# ClockCubed_v1.net
KiCad netlist of a schematic drawn in EAGLE
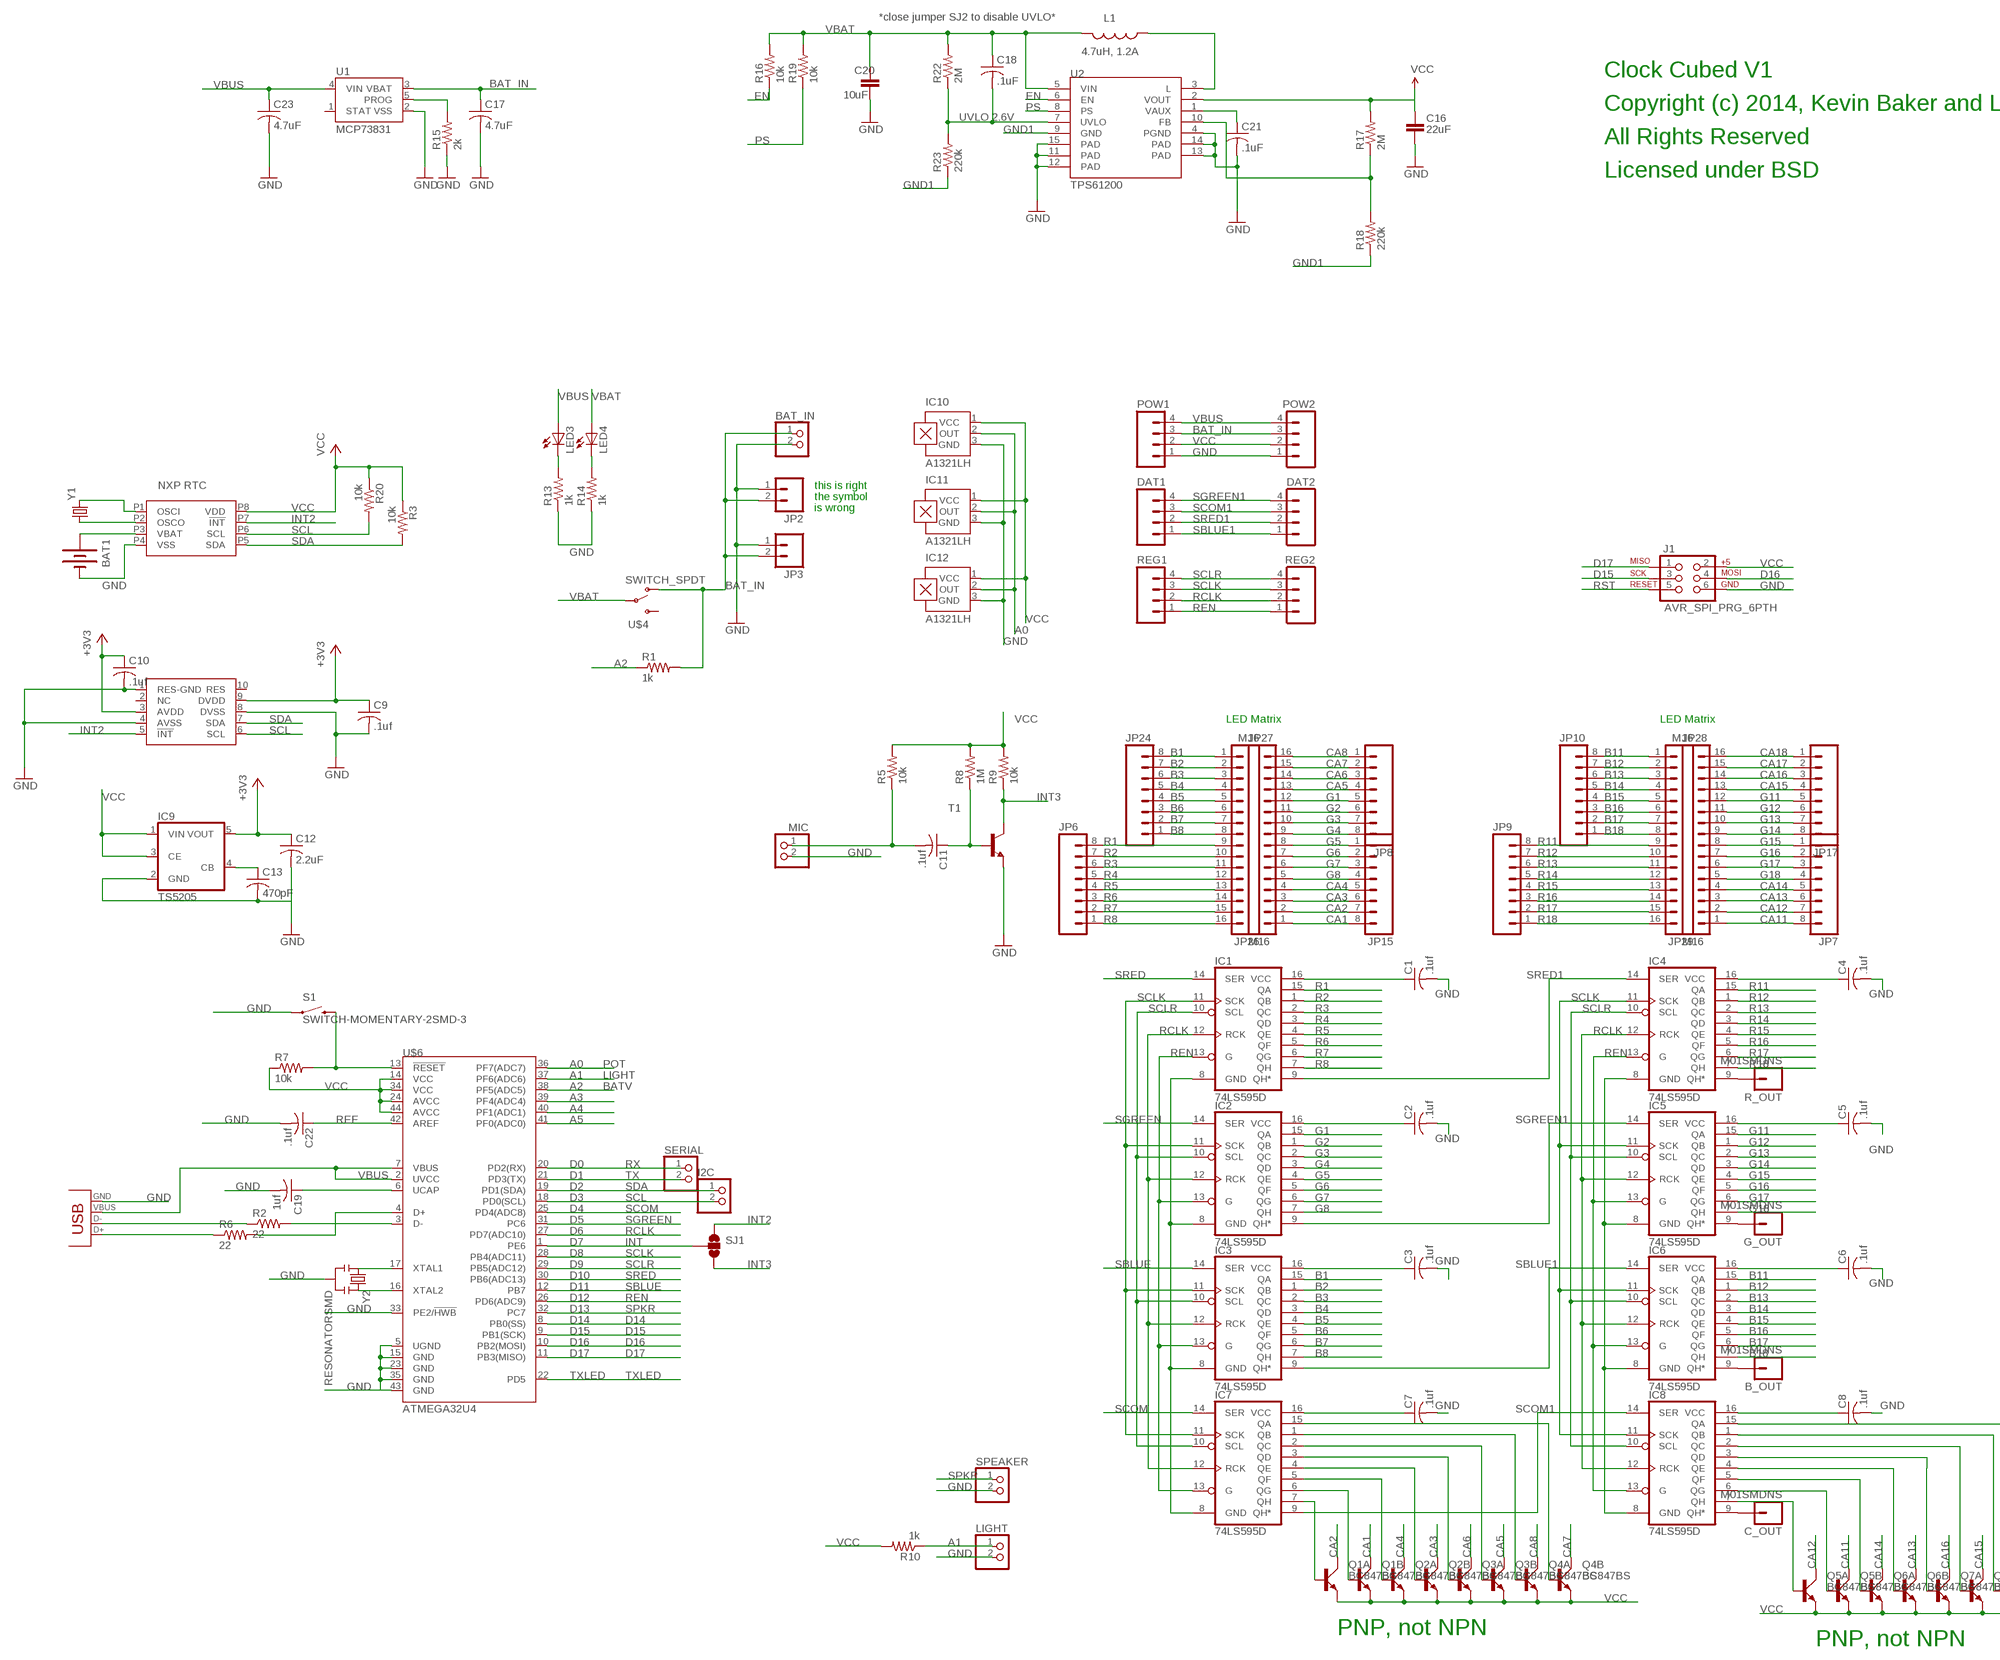
[diagram p0: schematic, sheet 1, part 1 of 2]
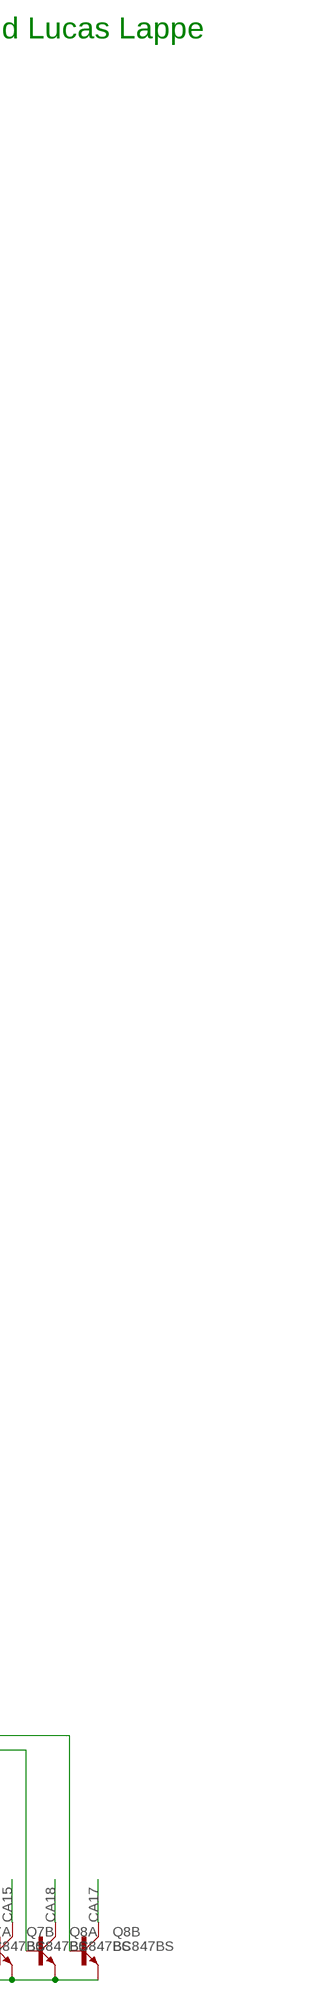
[diagram p1: schematic, sheet 1, part 2 of 2]

(export (version "E")
  (design (tool "Eeschema 10.0.6"))
  (components
    (comp (ref "BAT1")
      (value "BATTERY12MM")
      (footprint "eagle-import:BATTCON_12MM")
      (libsource (lib "eagle-import") (part "BATTERY12MM"))
    )
    (comp (ref "BAT_IN")
      (value "PINHD-1X2")
      (footprint "eagle-import:1X02")
      (libsource (lib "eagle-import") (part "PINHD-1X2"))
    )
    (comp (ref "B_OUT")
      (value "M01SMDNS")
      (footprint "eagle-import:1X01NS")
      (libsource (lib "eagle-import") (part "M01SMDNS"))
    )
    (comp (ref "C1")
      (value ".1uf")
      (footprint "eagle-import:C0603")
      (libsource (lib "eagle-import") (part "C-USC0603"))
    )
    (comp (ref "C2")
      (value ".1uf")
      (footprint "eagle-import:C0603")
      (libsource (lib "eagle-import") (part "C-USC0603"))
    )
    (comp (ref "C3")
      (value ".1uf")
      (footprint "eagle-import:C0603")
      (libsource (lib "eagle-import") (part "C-USC0603"))
    )
    (comp (ref "C4")
      (value ".1uf")
      (footprint "eagle-import:C0603")
      (libsource (lib "eagle-import") (part "C-USC0603"))
    )
    (comp (ref "C5")
      (value ".1uf")
      (footprint "eagle-import:C0603")
      (libsource (lib "eagle-import") (part "C-USC0603"))
    )
    (comp (ref "C6")
      (value ".1uf")
      (footprint "eagle-import:C0603")
      (libsource (lib "eagle-import") (part "C-USC0603"))
    )
    (comp (ref "C7")
      (value ".1uf")
      (footprint "eagle-import:C0603")
      (libsource (lib "eagle-import") (part "C-USC0603"))
    )
    (comp (ref "C8")
      (value ".1uf")
      (footprint "eagle-import:C0603")
      (libsource (lib "eagle-import") (part "C-USC0603"))
    )
    (comp (ref "C9")
      (value ".1uf")
      (footprint "eagle-import:C0603")
      (libsource (lib "eagle-import") (part "C-USC0603"))
    )
    (comp (ref "C10")
      (value ".1uf")
      (footprint "eagle-import:C0603")
      (libsource (lib "eagle-import") (part "C-USC0603"))
    )
    (comp (ref "C11")
      (value ".1uf")
      (footprint "eagle-import:C0603")
      (libsource (lib "eagle-import") (part "C-USC0603"))
    )
    (comp (ref "C12")
      (value "2.2uF")
      (footprint "eagle-import:C0603")
      (libsource (lib "eagle-import") (part "C-USC0603"))
    )
    (comp (ref "C13")
      (value "470pF")
      (footprint "eagle-import:C0603")
      (libsource (lib "eagle-import") (part "C-USC0603"))
    )
    (comp (ref "C16")
      (value "22uF")
      (footprint "eagle-import:0805")
      (libsource (lib "eagle-import") (part "CAP0805"))
    )
    (comp (ref "C17")
      (value "4.7uF")
      (footprint "eagle-import:C0603")
      (libsource (lib "eagle-import") (part "C-USC0603"))
    )
    (comp (ref "C18")
      (value ".1uF")
      (footprint "eagle-import:C0603")
      (libsource (lib "eagle-import") (part "C-USC0603"))
    )
    (comp (ref "C19")
      (value "1uf")
      (footprint "eagle-import:C0603")
      (libsource (lib "eagle-import") (part "C-USC0603"))
    )
    (comp (ref "C20")
      (value "10uF")
      (footprint "eagle-import:1206")
      (libsource (lib "eagle-import") (part "CAP1206"))
    )
    (comp (ref "C21")
      (value ".1uF")
      (footprint "eagle-import:C0603")
      (libsource (lib "eagle-import") (part "C-USC0603"))
    )
    (comp (ref "C22")
      (value ".1uf")
      (footprint "eagle-import:C0603")
      (libsource (lib "eagle-import") (part "C-USC0603"))
    )
    (comp (ref "C23")
      (value "4.7uF")
      (footprint "eagle-import:C0603")
      (libsource (lib "eagle-import") (part "C-USC0603"))
    )
    (comp (ref "C_OUT")
      (value "M01SMDNS")
      (footprint "eagle-import:1X01NS")
      (libsource (lib "eagle-import") (part "M01SMDNS"))
    )
    (comp (ref "DAT1")
      (value "M04PTH")
      (footprint "eagle-import:1X04")
      (libsource (lib "eagle-import") (part "M04PTH"))
    )
    (comp (ref "DAT2")
      (value "M04PTH")
      (footprint "eagle-import:1X04")
      (libsource (lib "eagle-import") (part "M04PTH"))
    )
    (comp (ref "G_OUT")
      (value "M01SMDNS")
      (footprint "eagle-import:1X01NS")
      (libsource (lib "eagle-import") (part "M01SMDNS"))
    )
    (comp (ref "I2C")
      (value "PINHD-1X2")
      (footprint "eagle-import:1X02")
      (libsource (lib "eagle-import") (part "PINHD-1X2"))
    )
    (comp (ref "IC1")
      (value "74LS595D")
      (footprint "eagle-import:SO16")
      (libsource (lib "eagle-import") (part "74595DLS"))
    )
    (comp (ref "IC2")
      (value "74LS595D")
      (footprint "eagle-import:SO16")
      (libsource (lib "eagle-import") (part "74595DLS"))
    )
    (comp (ref "IC3")
      (value "74LS595D")
      (footprint "eagle-import:SO16")
      (libsource (lib "eagle-import") (part "74595DLS"))
    )
    (comp (ref "IC4")
      (value "74LS595D")
      (footprint "eagle-import:SO16")
      (libsource (lib "eagle-import") (part "74595DLS"))
    )
    (comp (ref "IC5")
      (value "74LS595D")
      (footprint "eagle-import:SO16")
      (libsource (lib "eagle-import") (part "74595DLS"))
    )
    (comp (ref "IC6")
      (value "74LS595D")
      (footprint "eagle-import:SO16")
      (libsource (lib "eagle-import") (part "74595DLS"))
    )
    (comp (ref "IC7")
      (value "74LS595D")
      (footprint "eagle-import:SO16")
      (libsource (lib "eagle-import") (part "74595DLS"))
    )
    (comp (ref "IC8")
      (value "74LS595D")
      (footprint "eagle-import:SO16")
      (libsource (lib "eagle-import") (part "74595DLS"))
    )
    (comp (ref "IC9")
      (value "TS5205")
      (footprint "eagle-import:SOT25")
      (libsource (lib "eagle-import") (part "TS5205"))
    )
    (comp (ref "IC10")
      (value "A1321LH")
      (footprint "eagle-import:SOT23-W")
      (fields (field (name "MF") "ALLEGRO MICROSYSTEMS, INC.") (field (name "MPN") "A1321LLHLT-T"))
      (libsource (lib "eagle-import") (part "A13?LH21"))
    )
    (comp (ref "IC11")
      (value "A1321LH")
      (footprint "eagle-import:SOT23-W")
      (fields (field (name "MF") "ALLEGRO MICROSYSTEMS, INC.") (field (name "MPN") "A1321LLHLT-T"))
      (libsource (lib "eagle-import") (part "A13?LH21"))
    )
    (comp (ref "IC12")
      (value "A1321LH")
      (footprint "eagle-import:SOT23-W")
      (fields (field (name "MF") "ALLEGRO MICROSYSTEMS, INC.") (field (name "MPN") "A1321LLHLT-T"))
      (libsource (lib "eagle-import") (part "A13?LH21"))
    )
    (comp (ref "J1")
      (value "AVR_SPI_PRG_6PTH")
      (footprint "eagle-import:2X3")
      (libsource (lib "eagle-import") (part "AVR_SPI_PRG_6PTH"))
    )
    (comp (ref "JP2")
      (value "M02JST-PTH-2")
      (footprint "eagle-import:JST-2-PTH")
      (libsource (lib "eagle-import") (part "M02JST-PTH-2"))
    )
    (comp (ref "JP3")
      (value "M02JST-PTH-2")
      (footprint "eagle-import:JST-2-PTH")
      (libsource (lib "eagle-import") (part "M02JST-PTH-2"))
    )
    (comp (ref "JP6")
      (value "M08SMD-COMBO")
      (footprint "eagle-import:1X08_SMD_COMBINED")
      (libsource (lib "eagle-import") (part "M08SMD-COMBO"))
    )
    (comp (ref "JP7")
      (value "M08SMD-COMBO")
      (footprint "eagle-import:1X08_SMD_COMBINED")
      (libsource (lib "eagle-import") (part "M08SMD-COMBO"))
    )
    (comp (ref "JP8")
      (value "M08SMD-COMBO")
      (footprint "eagle-import:1X08_SMD_COMBINED")
      (libsource (lib "eagle-import") (part "M08SMD-COMBO"))
    )
    (comp (ref "JP9")
      (value "M08SMD-COMBO")
      (footprint "eagle-import:1X08_SMD_COMBINED")
      (libsource (lib "eagle-import") (part "M08SMD-COMBO"))
    )
    (comp (ref "JP10")
      (value "M08SMD-COMBO")
      (footprint "eagle-import:1X08_SMD_COMBINED")
      (libsource (lib "eagle-import") (part "M08SMD-COMBO"))
    )
    (comp (ref "JP15")
      (value "M08SMD-COMBO")
      (footprint "eagle-import:1X08_SMD_COMBINED")
      (libsource (lib "eagle-import") (part "M08SMD-COMBO"))
    )
    (comp (ref "JP17")
      (value "M08SMD-COMBO")
      (footprint "eagle-import:1X08_SMD_COMBINED")
      (libsource (lib "eagle-import") (part "M08SMD-COMBO"))
    )
    (comp (ref "JP24")
      (value "M08SMD-COMBO")
      (footprint "eagle-import:1X08_SMD_COMBINED")
      (libsource (lib "eagle-import") (part "M08SMD-COMBO"))
    )
    (comp (ref "JP26")
      (value "M16")
      (footprint "eagle-import:1X16_NS")
      (libsource (lib "eagle-import") (part "M16"))
    )
    (comp (ref "JP27")
      (value "M16")
      (footprint "eagle-import:1X16_NS")
      (libsource (lib "eagle-import") (part "M16"))
    )
    (comp (ref "JP28")
      (value "M16")
      (footprint "eagle-import:1X16_NS")
      (libsource (lib "eagle-import") (part "M16"))
    )
    (comp (ref "JP29")
      (value "M16")
      (footprint "eagle-import:1X16_NS")
      (libsource (lib "eagle-import") (part "M16"))
    )
    (comp (ref "L1")
      (value "4.7uH, 1.2A")
      (footprint "eagle-import:CDRH2D09")
      (libsource (lib "eagle-import") (part "INDUCTOR."))
    )
    (comp (ref "LED3")
      (value "LEDCHIPLED_0805")
      (footprint "eagle-import:CHIPLED_0805")
      (libsource (lib "eagle-import") (part "LEDCHIPLED_0805"))
    )
    (comp (ref "LED4")
      (value "LEDCHIPLED_0805")
      (footprint "eagle-import:CHIPLED_0805")
      (libsource (lib "eagle-import") (part "LEDCHIPLED_0805"))
    )
    (comp (ref "LIGHT")
      (value "PINHD-1X2")
      (footprint "eagle-import:1X02")
      (libsource (lib "eagle-import") (part "PINHD-1X2"))
    )
    (comp (ref "MIC")
      (value "PINHD-1X2")
      (footprint "eagle-import:1X02")
      (libsource (lib "eagle-import") (part "PINHD-1X2"))
    )
    (comp (ref "POW1")
      (value "M04PTH")
      (footprint "eagle-import:1X04")
      (libsource (lib "eagle-import") (part "M04PTH"))
    )
    (comp (ref "POW2")
      (value "M04PTH")
      (footprint "eagle-import:1X04")
      (libsource (lib "eagle-import") (part "M04PTH"))
    )
    (comp (ref "Q1")
      (value "BC847BS")
      (footprint "eagle-import:SOT363_PHILIPS")
      (libsource (lib "eagle-import") (part "BC847BS"))
    )
    (comp (ref "Q2")
      (value "BC847BS")
      (footprint "eagle-import:SOT363_PHILIPS")
      (libsource (lib "eagle-import") (part "BC847BS"))
    )
    (comp (ref "Q3")
      (value "BC847BS")
      (footprint "eagle-import:SOT363_PHILIPS")
      (libsource (lib "eagle-import") (part "BC847BS"))
    )
    (comp (ref "Q4")
      (value "BC847BS")
      (footprint "eagle-import:SOT363_PHILIPS")
      (libsource (lib "eagle-import") (part "BC847BS"))
    )
    (comp (ref "Q5")
      (value "BC847BS")
      (footprint "eagle-import:SOT363_PHILIPS")
      (libsource (lib "eagle-import") (part "BC847BS"))
    )
    (comp (ref "Q6")
      (value "BC847BS")
      (footprint "eagle-import:SOT363_PHILIPS")
      (libsource (lib "eagle-import") (part "BC847BS"))
    )
    (comp (ref "Q7")
      (value "BC847BS")
      (footprint "eagle-import:SOT363_PHILIPS")
      (libsource (lib "eagle-import") (part "BC847BS"))
    )
    (comp (ref "Q8")
      (value "BC847BS")
      (footprint "eagle-import:SOT363_PHILIPS")
      (libsource (lib "eagle-import") (part "BC847BS"))
    )
    (comp (ref "R1")
      (value "1k")
      (footprint "eagle-import:0603-RES")
      (libsource (lib "eagle-import") (part "RESISTOR0603-RES"))
    )
    (comp (ref "R2")
      (value "22")
      (footprint "eagle-import:0603-RES")
      (libsource (lib "eagle-import") (part "RESISTOR0603-RES"))
    )
    (comp (ref "R3")
      (value "10k")
      (footprint "eagle-import:0603-RES")
      (libsource (lib "eagle-import") (part "RESISTOR0603-RES"))
    )
    (comp (ref "R5")
      (value "10k")
      (footprint "eagle-import:0603-RES")
      (libsource (lib "eagle-import") (part "RESISTOR0603-RES"))
    )
    (comp (ref "R6")
      (value "22")
      (footprint "eagle-import:0603-RES")
      (libsource (lib "eagle-import") (part "RESISTOR0603-RES"))
    )
    (comp (ref "R7")
      (value "10k")
      (footprint "eagle-import:0603-RES")
      (libsource (lib "eagle-import") (part "RESISTOR0603-RES"))
    )
    (comp (ref "R8")
      (value "1M")
      (footprint "eagle-import:0603-RES")
      (libsource (lib "eagle-import") (part "RESISTOR0603-RES"))
    )
    (comp (ref "R9")
      (value "10k")
      (footprint "eagle-import:0603-RES")
      (libsource (lib "eagle-import") (part "RESISTOR0603-RES"))
    )
    (comp (ref "R10")
      (value "1k")
      (footprint "eagle-import:0603-RES")
      (libsource (lib "eagle-import") (part "RESISTOR0603-RES"))
    )
    (comp (ref "R13")
      (value "1k")
      (footprint "eagle-import:0603-RES")
      (libsource (lib "eagle-import") (part "RESISTOR0603-RES"))
    )
    (comp (ref "R14")
      (value "1k")
      (footprint "eagle-import:0603-RES")
      (libsource (lib "eagle-import") (part "RESISTOR0603-RES"))
    )
    (comp (ref "R15")
      (value "2k")
      (footprint "eagle-import:0603-RES")
      (libsource (lib "eagle-import") (part "RESISTOR0603-RES"))
    )
    (comp (ref "R16")
      (value "10k")
      (footprint "eagle-import:0603-RES")
      (libsource (lib "eagle-import") (part "RESISTOR0603-RES"))
    )
    (comp (ref "R17")
      (value "2M")
      (footprint "eagle-import:0603-RES")
      (libsource (lib "eagle-import") (part "RESISTOR0603-RES"))
    )
    (comp (ref "R18")
      (value "220k")
      (footprint "eagle-import:0603-RES")
      (libsource (lib "eagle-import") (part "RESISTOR0603-RES"))
    )
    (comp (ref "R19")
      (value "10k")
      (footprint "eagle-import:0603-RES")
      (libsource (lib "eagle-import") (part "RESISTOR0603-RES"))
    )
    (comp (ref "R20")
      (value "10k")
      (footprint "eagle-import:0603-RES")
      (libsource (lib "eagle-import") (part "RESISTOR0603-RES"))
    )
    (comp (ref "R22")
      (value "2M")
      (footprint "eagle-import:0603-RES")
      (libsource (lib "eagle-import") (part "RESISTOR0603-RES"))
    )
    (comp (ref "R23")
      (value "220k")
      (footprint "eagle-import:0603-RES")
      (libsource (lib "eagle-import") (part "RESISTOR0603-RES"))
    )
    (comp (ref "REG1")
      (value "M04PTH")
      (footprint "eagle-import:1X04")
      (libsource (lib "eagle-import") (part "M04PTH"))
    )
    (comp (ref "REG2")
      (value "M04PTH")
      (footprint "eagle-import:1X04")
      (libsource (lib "eagle-import") (part "M04PTH"))
    )
    (comp (ref "R_OUT")
      (value "M01SMDNS")
      (footprint "eagle-import:1X01NS")
      (libsource (lib "eagle-import") (part "M01SMDNS"))
    )
    (comp (ref "S1")
      (value "SWITCH-MOMENTARY-2SMD-3")
      (footprint "eagle-import:TACTILE_SWITCH_SMD-3")
      (libsource (lib "eagle-import") (part "SWITCH-MOMENTARY-2SMD-3"))
    )
    (comp (ref "SERIAL")
      (value "PINHD-1X2")
      (footprint "eagle-import:1X02")
      (libsource (lib "eagle-import") (part "PINHD-1X2"))
    )
    (comp (ref "SJ1")
      (value "SOLDERJUMPER_2WAYS")
      (footprint "eagle-import:SJ_3")
      (libsource (lib "eagle-import") (part "SOLDERJUMPER_2WAYS"))
    )
    (comp (ref "SPEAKER")
      (value "PINHD-1X2")
      (footprint "eagle-import:1X02")
      (libsource (lib "eagle-import") (part "PINHD-1X2"))
    )
    (comp (ref "T1")
      (value "-NPN-SOT23-EBC")
      (footprint "eagle-import:SOT23-EBC")
      (libsource (lib "eagle-import") (part "-NPN-SOT23-EBC"))
    )
    (comp (ref "U$1")
      (value "USB_MICROB")
      (footprint "eagle-import:USB-MICROB")
      (libsource (lib "eagle-import") (part "USB_MICROB"))
    )
    (comp (ref "U$2")
      (value "MMA7660FC")
      (footprint "eagle-import:DFN-10")
      (libsource (lib "eagle-import") (part "MMA7660FC"))
    )
    (comp (ref "U$3")
      (value "NXP-RTC")
      (footprint "eagle-import:HVSON8")
      (libsource (lib "eagle-import") (part "NXP-RTC"))
    )
    (comp (ref "U$4")
      (value "SWITCH_SPDT")
      (footprint "eagle-import:KPS-1290")
      (libsource (lib "eagle-import") (part "SWITCH_SPDT"))
    )
    (comp (ref "U$6")
      (value "ATMEGA32U4")
      (footprint "eagle-import:TQFP44")
      (libsource (lib "eagle-import") (part "ATMEGA32U4"))
    )
    (comp (ref "U1")
      (value "MCP73831")
      (footprint "eagle-import:SOT23-5")
      (libsource (lib "eagle-import") (part "MCP73831"))
    )
    (comp (ref "U2")
      (value "TPS61200")
      (footprint "eagle-import:QFN-10_PAD")
      (libsource (lib "eagle-import") (part "TPS61200"))
    )
    (comp (ref "Y1")
      (value "CRYSTAL5X2")
      (footprint "eagle-import:CRYSTAL-SMD-5X2")
      (libsource (lib "eagle-import") (part "CRYSTAL5X2"))
    )
    (comp (ref "Y2")
      (value "RESONATORSMD")
      (footprint "eagle-import:RESONATOR-SMD")
      (libsource (lib "eagle-import") (part "RESONATORSMD"))
    )
  )
  (nets
    (net (code "1") (name "+3V3") (class "Default")
      (node (ref "C10") (pin "1") (pinfunction "1_1") (pintype "passive"))
      (node (ref "C12") (pin "1") (pinfunction "1_1") (pintype "passive"))
      (node (ref "C9") (pin "1") (pinfunction "1_1") (pintype "passive"))
      (node (ref "IC9") (pin "5") (pinfunction "VOUT_5") (pintype "passive"))
      (node (ref "U$2") (pin "3") (pinfunction "AVDD_3") (pintype "bidirectional"))
      (node (ref "U$2") (pin "9") (pinfunction "DVDD_9") (pintype "bidirectional"))
    )
    (net (code "2") (name "/A0") (class "Default")
      (node (ref "IC10") (pin "2") (pinfunction "OUT_2") (pintype "output"))
      (node (ref "IC11") (pin "2") (pinfunction "OUT_2") (pintype "output"))
      (node (ref "IC12") (pin "2") (pinfunction "OUT_2") (pintype "output"))
      (node (ref "U$6") (pin "36") (pinfunction "PF7(ADC7)_36") (pintype "bidirectional"))
    )
    (net (code "3") (name "/A1") (class "Default")
      (node (ref "LIGHT") (pin "1") (pinfunction "1_1") (pintype "passive"))
      (node (ref "R10") (pin "1") (pinfunction "1_1") (pintype "passive"))
      (node (ref "U$6") (pin "37") (pinfunction "PF6(ADC6)_37") (pintype "bidirectional"))
    )
    (net (code "4") (name "/A2") (class "Default")
      (node (ref "R1") (pin "1") (pinfunction "1_1") (pintype "passive"))
      (node (ref "U$6") (pin "38") (pinfunction "PF5(ADC5)_38") (pintype "bidirectional"))
    )
    (net (code "5") (name "/A3") (class "Default")
      (node (ref "U$6") (pin "39") (pinfunction "PF4(ADC4)_39") (pintype "bidirectional"))
    )
    (net (code "6") (name "/A4") (class "Default")
      (node (ref "U$6") (pin "40") (pinfunction "PF1(ADC1)_40") (pintype "bidirectional"))
    )
    (net (code "7") (name "/A5") (class "Default")
      (node (ref "U$6") (pin "41") (pinfunction "PF0(ADC0)_41") (pintype "bidirectional"))
    )
    (net (code "8") (name "/B1") (class "Default")
      (node (ref "IC3") (pin "15") (pinfunction "QA_15") (pintype "tri_state"))
      (node (ref "JP24") (pin "8") (pinfunction "8_8") (pintype "passive"))
      (node (ref "JP26") (pin "1") (pinfunction "1_1") (pintype "passive"))
    )
    (net (code "9") (name "/B2") (class "Default")
      (node (ref "IC3") (pin "1") (pinfunction "QB_1") (pintype "tri_state"))
      (node (ref "JP24") (pin "7") (pinfunction "7_7") (pintype "passive"))
      (node (ref "JP26") (pin "2") (pinfunction "2_2") (pintype "passive"))
    )
    (net (code "10") (name "/B3") (class "Default")
      (node (ref "IC3") (pin "2") (pinfunction "QC_2") (pintype "tri_state"))
      (node (ref "JP24") (pin "6") (pinfunction "6_6") (pintype "passive"))
      (node (ref "JP26") (pin "3") (pinfunction "3_3") (pintype "passive"))
    )
    (net (code "11") (name "/B4") (class "Default")
      (node (ref "IC3") (pin "3") (pinfunction "QD_3") (pintype "tri_state"))
      (node (ref "JP24") (pin "5") (pinfunction "5_5") (pintype "passive"))
      (node (ref "JP26") (pin "4") (pinfunction "4_4") (pintype "passive"))
    )
    (net (code "12") (name "/B5") (class "Default")
      (node (ref "IC3") (pin "4") (pinfunction "QE_4") (pintype "tri_state"))
      (node (ref "JP24") (pin "4") (pinfunction "4_4") (pintype "passive"))
      (node (ref "JP26") (pin "5") (pinfunction "5_5") (pintype "passive"))
    )
    (net (code "13") (name "/B6") (class "Default")
      (node (ref "IC3") (pin "5") (pinfunction "QF_5") (pintype "tri_state"))
      (node (ref "JP24") (pin "3") (pinfunction "3_3") (pintype "passive"))
      (node (ref "JP26") (pin "6") (pinfunction "6_6") (pintype "passive"))
    )
    (net (code "14") (name "/B7") (class "Default")
      (node (ref "IC3") (pin "6") (pinfunction "QG_6") (pintype "tri_state"))
      (node (ref "JP24") (pin "2") (pinfunction "2_2") (pintype "passive"))
      (node (ref "JP26") (pin "7") (pinfunction "7_7") (pintype "passive"))
    )
    (net (code "15") (name "/B8") (class "Default")
      (node (ref "IC3") (pin "7") (pinfunction "QH_7") (pintype "tri_state"))
      (node (ref "JP24") (pin "1") (pinfunction "1_1") (pintype "passive"))
      (node (ref "JP26") (pin "8") (pinfunction "8_8") (pintype "passive"))
    )
    (net (code "16") (name "/B11") (class "Default")
      (node (ref "IC6") (pin "15") (pinfunction "QA_15") (pintype "tri_state"))
      (node (ref "JP10") (pin "8") (pinfunction "8_8") (pintype "passive"))
      (node (ref "JP29") (pin "1") (pinfunction "1_1") (pintype "passive"))
    )
    (net (code "17") (name "/B12") (class "Default")
      (node (ref "IC6") (pin "1") (pinfunction "QB_1") (pintype "tri_state"))
      (node (ref "JP10") (pin "7") (pinfunction "7_7") (pintype "passive"))
      (node (ref "JP29") (pin "2") (pinfunction "2_2") (pintype "passive"))
    )
    (net (code "18") (name "/B13") (class "Default")
      (node (ref "IC6") (pin "2") (pinfunction "QC_2") (pintype "tri_state"))
      (node (ref "JP10") (pin "6") (pinfunction "6_6") (pintype "passive"))
      (node (ref "JP29") (pin "3") (pinfunction "3_3") (pintype "passive"))
    )
    (net (code "19") (name "/B14") (class "Default")
      (node (ref "IC6") (pin "3") (pinfunction "QD_3") (pintype "tri_state"))
      (node (ref "JP10") (pin "5") (pinfunction "5_5") (pintype "passive"))
      (node (ref "JP29") (pin "4") (pinfunction "4_4") (pintype "passive"))
    )
    (net (code "20") (name "/B15") (class "Default")
      (node (ref "IC6") (pin "4") (pinfunction "QE_4") (pintype "tri_state"))
      (node (ref "JP10") (pin "4") (pinfunction "4_4") (pintype "passive"))
      (node (ref "JP29") (pin "5") (pinfunction "5_5") (pintype "passive"))
    )
    (net (code "21") (name "/B16") (class "Default")
      (node (ref "IC6") (pin "5") (pinfunction "QF_5") (pintype "tri_state"))
      (node (ref "JP10") (pin "3") (pinfunction "3_3") (pintype "passive"))
      (node (ref "JP29") (pin "6") (pinfunction "6_6") (pintype "passive"))
    )
    (net (code "22") (name "/B17") (class "Default")
      (node (ref "IC6") (pin "6") (pinfunction "QG_6") (pintype "tri_state"))
      (node (ref "JP10") (pin "2") (pinfunction "2_2") (pintype "passive"))
      (node (ref "JP29") (pin "7") (pinfunction "7_7") (pintype "passive"))
    )
    (net (code "23") (name "/B18") (class "Default")
      (node (ref "IC6") (pin "7") (pinfunction "QH_7") (pintype "tri_state"))
      (node (ref "JP10") (pin "1") (pinfunction "1_1") (pintype "passive"))
      (node (ref "JP29") (pin "8") (pinfunction "8_8") (pintype "passive"))
    )
    (net (code "24") (name "/BAT_IN") (class "Default")
      (node (ref "BAT_IN") (pin "1") (pinfunction "1_1") (pintype "passive"))
      (node (ref "C17") (pin "1") (pinfunction "1_1") (pintype "passive"))
      (node (ref "JP2") (pin "2") (pinfunction "2_2") (pintype "passive"))
      (node (ref "JP3") (pin "2") (pinfunction "2_2") (pintype "passive"))
      (node (ref "POW1") (pin "3") (pinfunction "3_3") (pintype "passive"))
      (node (ref "POW2") (pin "3") (pinfunction "3_3") (pintype "passive"))
      (node (ref "R1") (pin "2") (pinfunction "2_2") (pintype "passive"))
      (node (ref "U$4") (pin "O") (pinfunction "O_O") (pintype "passive"))
      (node (ref "U1") (pin "3") (pinfunction "VBAT_3") (pintype "power_in"))
    )
    (net (code "25") (name "/CA1") (class "Default")
      (node (ref "JP15") (pin "8") (pinfunction "8_8") (pintype "passive"))
      (node (ref "JP27") (pin "1") (pinfunction "1_1") (pintype "passive"))
      (node (ref "Q1") (pin "3") (pinfunction "C_3") (pintype "passive"))
    )
    (net (code "26") (name "/CA2") (class "Default")
      (node (ref "JP15") (pin "7") (pinfunction "7_7") (pintype "passive"))
      (node (ref "JP27") (pin "2") (pinfunction "2_2") (pintype "passive"))
      (node (ref "Q1") (pin "6") (pinfunction "C_6") (pintype "passive"))
    )
    (net (code "27") (name "/CA3") (class "Default")
      (node (ref "JP15") (pin "6") (pinfunction "6_6") (pintype "passive"))
      (node (ref "JP27") (pin "3") (pinfunction "3_3") (pintype "passive"))
      (node (ref "Q2") (pin "3") (pinfunction "C_3") (pintype "passive"))
    )
    (net (code "28") (name "/CA4") (class "Default")
      (node (ref "JP15") (pin "5") (pinfunction "5_5") (pintype "passive"))
      (node (ref "JP27") (pin "4") (pinfunction "4_4") (pintype "passive"))
      (node (ref "Q2") (pin "6") (pinfunction "C_6") (pintype "passive"))
    )
    (net (code "29") (name "/CA5") (class "Default")
      (node (ref "JP27") (pin "13") (pinfunction "13_13") (pintype "passive"))
      (node (ref "JP8") (pin "4") (pinfunction "4_4") (pintype "passive"))
      (node (ref "Q3") (pin "3") (pinfunction "C_3") (pintype "passive"))
    )
    (net (code "30") (name "/CA6") (class "Default")
      (node (ref "JP27") (pin "14") (pinfunction "14_14") (pintype "passive"))
      (node (ref "JP8") (pin "3") (pinfunction "3_3") (pintype "passive"))
      (node (ref "Q3") (pin "6") (pinfunction "C_6") (pintype "passive"))
    )
    (net (code "31") (name "/CA7") (class "Default")
      (node (ref "JP27") (pin "15") (pinfunction "15_15") (pintype "passive"))
      (node (ref "JP8") (pin "2") (pinfunction "2_2") (pintype "passive"))
      (node (ref "Q4") (pin "3") (pinfunction "C_3") (pintype "passive"))
    )
    (net (code "32") (name "/CA8") (class "Default")
      (node (ref "JP27") (pin "16") (pinfunction "16_16") (pintype "passive"))
      (node (ref "JP8") (pin "1") (pinfunction "1_1") (pintype "passive"))
      (node (ref "Q4") (pin "6") (pinfunction "C_6") (pintype "passive"))
    )
    (net (code "33") (name "/CA11") (class "Default")
      (node (ref "JP28") (pin "1") (pinfunction "1_1") (pintype "passive"))
      (node (ref "JP7") (pin "8") (pinfunction "8_8") (pintype "passive"))
      (node (ref "Q5") (pin "3") (pinfunction "C_3") (pintype "passive"))
    )
    (net (code "34") (name "/CA12") (class "Default")
      (node (ref "JP28") (pin "2") (pinfunction "2_2") (pintype "passive"))
      (node (ref "JP7") (pin "7") (pinfunction "7_7") (pintype "passive"))
      (node (ref "Q5") (pin "6") (pinfunction "C_6") (pintype "passive"))
    )
    (net (code "35") (name "/CA13") (class "Default")
      (node (ref "JP28") (pin "3") (pinfunction "3_3") (pintype "passive"))
      (node (ref "JP7") (pin "6") (pinfunction "6_6") (pintype "passive"))
      (node (ref "Q6") (pin "3") (pinfunction "C_3") (pintype "passive"))
    )
    (net (code "36") (name "/CA14") (class "Default")
      (node (ref "JP28") (pin "4") (pinfunction "4_4") (pintype "passive"))
      (node (ref "JP7") (pin "5") (pinfunction "5_5") (pintype "passive"))
      (node (ref "Q6") (pin "6") (pinfunction "C_6") (pintype "passive"))
    )
    (net (code "37") (name "/CA15") (class "Default")
      (node (ref "JP17") (pin "4") (pinfunction "4_4") (pintype "passive"))
      (node (ref "JP28") (pin "13") (pinfunction "13_13") (pintype "passive"))
      (node (ref "Q7") (pin "3") (pinfunction "C_3") (pintype "passive"))
    )
    (net (code "38") (name "/CA16") (class "Default")
      (node (ref "JP17") (pin "3") (pinfunction "3_3") (pintype "passive"))
      (node (ref "JP28") (pin "14") (pinfunction "14_14") (pintype "passive"))
      (node (ref "Q7") (pin "6") (pinfunction "C_6") (pintype "passive"))
    )
    (net (code "39") (name "/CA17") (class "Default")
      (node (ref "JP17") (pin "2") (pinfunction "2_2") (pintype "passive"))
      (node (ref "JP28") (pin "15") (pinfunction "15_15") (pintype "passive"))
      (node (ref "Q8") (pin "3") (pinfunction "C_3") (pintype "passive"))
    )
    (net (code "40") (name "/CA18") (class "Default")
      (node (ref "JP17") (pin "1") (pinfunction "1_1") (pintype "passive"))
      (node (ref "JP28") (pin "16") (pinfunction "16_16") (pintype "passive"))
      (node (ref "Q8") (pin "6") (pinfunction "C_6") (pintype "passive"))
    )
    (net (code "41") (name "/D14") (class "Default")
      (node (ref "U$6") (pin "8") (pinfunction "PB0(SS)_8") (pintype "bidirectional"))
    )
    (net (code "42") (name "/D15") (class "Default")
      (node (ref "J1") (pin "3") (pinfunction "3_3") (pintype "passive"))
      (node (ref "U$6") (pin "9") (pinfunction "PB1(SCK)_9") (pintype "bidirectional"))
    )
    (net (code "43") (name "/D16") (class "Default")
      (node (ref "J1") (pin "4") (pinfunction "4_4") (pintype "passive"))
      (node (ref "U$6") (pin "10") (pinfunction "PB2(MOSI)_10") (pintype "bidirectional"))
    )
    (net (code "44") (name "/D17") (class "Default")
      (node (ref "J1") (pin "1") (pinfunction "1_1") (pintype "passive"))
      (node (ref "U$6") (pin "11") (pinfunction "PB3(MISO)_11") (pintype "bidirectional"))
    )
    (net (code "45") (name "/EN") (class "Default")
      (node (ref "R16") (pin "1") (pinfunction "1_1") (pintype "passive"))
      (node (ref "U2") (pin "6") (pinfunction "EN_6") (pintype "input"))
    )
    (net (code "46") (name "/G1") (class "Default")
      (node (ref "IC2") (pin "15") (pinfunction "QA_15") (pintype "tri_state"))
      (node (ref "JP27") (pin "12") (pinfunction "12_12") (pintype "passive"))
      (node (ref "JP8") (pin "5") (pinfunction "5_5") (pintype "passive"))
    )
    (net (code "47") (name "/G2") (class "Default")
      (node (ref "IC2") (pin "1") (pinfunction "QB_1") (pintype "tri_state"))
      (node (ref "JP27") (pin "11") (pinfunction "11_11") (pintype "passive"))
      (node (ref "JP8") (pin "6") (pinfunction "6_6") (pintype "passive"))
    )
    (net (code "48") (name "/G3") (class "Default")
      (node (ref "IC2") (pin "2") (pinfunction "QC_2") (pintype "tri_state"))
      (node (ref "JP27") (pin "10") (pinfunction "10_10") (pintype "passive"))
      (node (ref "JP8") (pin "7") (pinfunction "7_7") (pintype "passive"))
    )
    (net (code "49") (name "/G4") (class "Default")
      (node (ref "IC2") (pin "3") (pinfunction "QD_3") (pintype "tri_state"))
      (node (ref "JP27") (pin "9") (pinfunction "9_9") (pintype "passive"))
      (node (ref "JP8") (pin "8") (pinfunction "8_8") (pintype "passive"))
    )
    (net (code "50") (name "/G5") (class "Default")
      (node (ref "IC2") (pin "4") (pinfunction "QE_4") (pintype "tri_state"))
      (node (ref "JP15") (pin "1") (pinfunction "1_1") (pintype "passive"))
      (node (ref "JP27") (pin "8") (pinfunction "8_8") (pintype "passive"))
    )
    (net (code "51") (name "/G6") (class "Default")
      (node (ref "IC2") (pin "5") (pinfunction "QF_5") (pintype "tri_state"))
      (node (ref "JP15") (pin "2") (pinfunction "2_2") (pintype "passive"))
      (node (ref "JP27") (pin "7") (pinfunction "7_7") (pintype "passive"))
    )
    (net (code "52") (name "/G7") (class "Default")
      (node (ref "IC2") (pin "6") (pinfunction "QG_6") (pintype "tri_state"))
      (node (ref "JP15") (pin "3") (pinfunction "3_3") (pintype "passive"))
      (node (ref "JP27") (pin "6") (pinfunction "6_6") (pintype "passive"))
    )
    (net (code "53") (name "/G8") (class "Default")
      (node (ref "IC2") (pin "7") (pinfunction "QH_7") (pintype "tri_state"))
      (node (ref "JP15") (pin "4") (pinfunction "4_4") (pintype "passive"))
      (node (ref "JP27") (pin "5") (pinfunction "5_5") (pintype "passive"))
    )
    (net (code "54") (name "/G11") (class "Default")
      (node (ref "IC5") (pin "15") (pinfunction "QA_15") (pintype "tri_state"))
      (node (ref "JP17") (pin "5") (pinfunction "5_5") (pintype "passive"))
      (node (ref "JP28") (pin "12") (pinfunction "12_12") (pintype "passive"))
    )
    (net (code "55") (name "/G12") (class "Default")
      (node (ref "IC5") (pin "1") (pinfunction "QB_1") (pintype "tri_state"))
      (node (ref "JP17") (pin "6") (pinfunction "6_6") (pintype "passive"))
      (node (ref "JP28") (pin "11") (pinfunction "11_11") (pintype "passive"))
    )
    (net (code "56") (name "/G13") (class "Default")
      (node (ref "IC5") (pin "2") (pinfunction "QC_2") (pintype "tri_state"))
      (node (ref "JP17") (pin "7") (pinfunction "7_7") (pintype "passive"))
      (node (ref "JP28") (pin "10") (pinfunction "10_10") (pintype "passive"))
    )
    (net (code "57") (name "/G14") (class "Default")
      (node (ref "IC5") (pin "3") (pinfunction "QD_3") (pintype "tri_state"))
      (node (ref "JP17") (pin "8") (pinfunction "8_8") (pintype "passive"))
      (node (ref "JP28") (pin "9") (pinfunction "9_9") (pintype "passive"))
    )
    (net (code "58") (name "/G15") (class "Default")
      (node (ref "IC5") (pin "4") (pinfunction "QE_4") (pintype "tri_state"))
      (node (ref "JP28") (pin "8") (pinfunction "8_8") (pintype "passive"))
      (node (ref "JP7") (pin "1") (pinfunction "1_1") (pintype "passive"))
    )
    (net (code "59") (name "/G16") (class "Default")
      (node (ref "IC5") (pin "5") (pinfunction "QF_5") (pintype "tri_state"))
      (node (ref "JP28") (pin "7") (pinfunction "7_7") (pintype "passive"))
      (node (ref "JP7") (pin "2") (pinfunction "2_2") (pintype "passive"))
    )
    (net (code "60") (name "/G17") (class "Default")
      (node (ref "IC5") (pin "6") (pinfunction "QG_6") (pintype "tri_state"))
      (node (ref "JP28") (pin "6") (pinfunction "6_6") (pintype "passive"))
      (node (ref "JP7") (pin "3") (pinfunction "3_3") (pintype "passive"))
    )
    (net (code "61") (name "/G18") (class "Default")
      (node (ref "IC5") (pin "7") (pinfunction "QH_7") (pintype "tri_state"))
      (node (ref "JP28") (pin "5") (pinfunction "5_5") (pintype "passive"))
      (node (ref "JP7") (pin "4") (pinfunction "4_4") (pintype "passive"))
    )
    (net (code "62") (name "/GND1") (class "Default")
      (node (ref "R18") (pin "1") (pinfunction "1_1") (pintype "passive"))
      (node (ref "R23") (pin "1") (pinfunction "1_1") (pintype "passive"))
      (node (ref "U2") (pin "9") (pinfunction "GND_9") (pintype "power_in"))
    )
    (net (code "63") (name "/INT") (class "Default")
      (node (ref "SJ1") (pin "2") (pinfunction "2_2") (pintype "passive"))
      (node (ref "U$6") (pin "1") (pinfunction "PE6_1") (pintype "bidirectional"))
    )
    (net (code "64") (name "/INT2") (class "Default")
      (node (ref "SJ1") (pin "1") (pinfunction "1_1") (pintype "passive"))
      (node (ref "U$2") (pin "5") (pinfunction "~{INT}_5") (pintype "bidirectional"))
      (node (ref "U$3") (pin "P7") (pinfunction "~{INT}_P7") (pintype "bidirectional"))
    )
    (net (code "65") (name "/INT3") (class "Default")
      (node (ref "R9") (pin "1") (pinfunction "1_1") (pintype "passive"))
      (node (ref "SJ1") (pin "3") (pinfunction "3_3") (pintype "passive"))
      (node (ref "T1") (pin "C") (pinfunction "C_C") (pintype "passive"))
    )
    (net (code "66") (name "/PS") (class "Default")
      (node (ref "R19") (pin "1") (pinfunction "1_1") (pintype "passive"))
      (node (ref "U2") (pin "8") (pinfunction "PS_8") (pintype "input"))
    )
    (net (code "67") (name "/R1") (class "Default")
      (node (ref "IC1") (pin "15") (pinfunction "QA_15") (pintype "tri_state"))
      (node (ref "JP26") (pin "9") (pinfunction "9_9") (pintype "passive"))
      (node (ref "JP6") (pin "8") (pinfunction "8_8") (pintype "passive"))
    )
    (net (code "68") (name "/R2") (class "Default")
      (node (ref "IC1") (pin "1") (pinfunction "QB_1") (pintype "tri_state"))
      (node (ref "JP26") (pin "10") (pinfunction "10_10") (pintype "passive"))
      (node (ref "JP6") (pin "7") (pinfunction "7_7") (pintype "passive"))
    )
    (net (code "69") (name "/R3") (class "Default")
      (node (ref "IC1") (pin "2") (pinfunction "QC_2") (pintype "tri_state"))
      (node (ref "JP26") (pin "11") (pinfunction "11_11") (pintype "passive"))
      (node (ref "JP6") (pin "6") (pinfunction "6_6") (pintype "passive"))
    )
    (net (code "70") (name "/R4") (class "Default")
      (node (ref "IC1") (pin "3") (pinfunction "QD_3") (pintype "tri_state"))
      (node (ref "JP26") (pin "12") (pinfunction "12_12") (pintype "passive"))
      (node (ref "JP6") (pin "5") (pinfunction "5_5") (pintype "passive"))
    )
    (net (code "71") (name "/R5") (class "Default")
      (node (ref "IC1") (pin "4") (pinfunction "QE_4") (pintype "tri_state"))
      (node (ref "JP26") (pin "13") (pinfunction "13_13") (pintype "passive"))
      (node (ref "JP6") (pin "4") (pinfunction "4_4") (pintype "passive"))
    )
    (net (code "72") (name "/R6") (class "Default")
      (node (ref "IC1") (pin "5") (pinfunction "QF_5") (pintype "tri_state"))
      (node (ref "JP26") (pin "14") (pinfunction "14_14") (pintype "passive"))
      (node (ref "JP6") (pin "3") (pinfunction "3_3") (pintype "passive"))
    )
    (net (code "73") (name "/R7") (class "Default")
      (node (ref "IC1") (pin "6") (pinfunction "QG_6") (pintype "tri_state"))
      (node (ref "JP26") (pin "15") (pinfunction "15_15") (pintype "passive"))
      (node (ref "JP6") (pin "2") (pinfunction "2_2") (pintype "passive"))
    )
    (net (code "74") (name "/R8") (class "Default")
      (node (ref "IC1") (pin "7") (pinfunction "QH_7") (pintype "tri_state"))
      (node (ref "JP26") (pin "16") (pinfunction "16_16") (pintype "passive"))
      (node (ref "JP6") (pin "1") (pinfunction "1_1") (pintype "passive"))
    )
    (net (code "75") (name "/R11") (class "Default")
      (node (ref "IC4") (pin "15") (pinfunction "QA_15") (pintype "tri_state"))
      (node (ref "JP29") (pin "9") (pinfunction "9_9") (pintype "passive"))
      (node (ref "JP9") (pin "8") (pinfunction "8_8") (pintype "passive"))
    )
    (net (code "76") (name "/R12") (class "Default")
      (node (ref "IC4") (pin "1") (pinfunction "QB_1") (pintype "tri_state"))
      (node (ref "JP29") (pin "10") (pinfunction "10_10") (pintype "passive"))
      (node (ref "JP9") (pin "7") (pinfunction "7_7") (pintype "passive"))
    )
    (net (code "77") (name "/R13") (class "Default")
      (node (ref "IC4") (pin "2") (pinfunction "QC_2") (pintype "tri_state"))
      (node (ref "JP29") (pin "11") (pinfunction "11_11") (pintype "passive"))
      (node (ref "JP9") (pin "6") (pinfunction "6_6") (pintype "passive"))
    )
    (net (code "78") (name "/R14") (class "Default")
      (node (ref "IC4") (pin "3") (pinfunction "QD_3") (pintype "tri_state"))
      (node (ref "JP29") (pin "12") (pinfunction "12_12") (pintype "passive"))
      (node (ref "JP9") (pin "5") (pinfunction "5_5") (pintype "passive"))
    )
    (net (code "79") (name "/R15") (class "Default")
      (node (ref "IC4") (pin "4") (pinfunction "QE_4") (pintype "tri_state"))
      (node (ref "JP29") (pin "13") (pinfunction "13_13") (pintype "passive"))
      (node (ref "JP9") (pin "4") (pinfunction "4_4") (pintype "passive"))
    )
    (net (code "80") (name "/R16") (class "Default")
      (node (ref "IC4") (pin "5") (pinfunction "QF_5") (pintype "tri_state"))
      (node (ref "JP29") (pin "14") (pinfunction "14_14") (pintype "passive"))
      (node (ref "JP9") (pin "3") (pinfunction "3_3") (pintype "passive"))
    )
    (net (code "81") (name "/R17") (class "Default")
      (node (ref "IC4") (pin "6") (pinfunction "QG_6") (pintype "tri_state"))
      (node (ref "JP29") (pin "15") (pinfunction "15_15") (pintype "passive"))
      (node (ref "JP9") (pin "2") (pinfunction "2_2") (pintype "passive"))
    )
    (net (code "82") (name "/R18") (class "Default")
      (node (ref "IC4") (pin "7") (pinfunction "QH_7") (pintype "tri_state"))
      (node (ref "JP29") (pin "16") (pinfunction "16_16") (pintype "passive"))
      (node (ref "JP9") (pin "1") (pinfunction "1_1") (pintype "passive"))
    )
    (net (code "83") (name "/RCLK") (class "Default")
      (node (ref "IC1") (pin "12") (pinfunction "RCK_12") (pintype "input"))
      (node (ref "IC2") (pin "12") (pinfunction "RCK_12") (pintype "input"))
      (node (ref "IC3") (pin "12") (pinfunction "RCK_12") (pintype "input"))
      (node (ref "IC4") (pin "12") (pinfunction "RCK_12") (pintype "input"))
      (node (ref "IC5") (pin "12") (pinfunction "RCK_12") (pintype "input"))
      (node (ref "IC6") (pin "12") (pinfunction "RCK_12") (pintype "input"))
      (node (ref "IC7") (pin "12") (pinfunction "RCK_12") (pintype "input"))
      (node (ref "IC8") (pin "12") (pinfunction "RCK_12") (pintype "input"))
      (node (ref "REG1") (pin "2") (pinfunction "2_2") (pintype "passive"))
      (node (ref "REG2") (pin "2") (pinfunction "2_2") (pintype "passive"))
      (node (ref "U$6") (pin "27") (pinfunction "PD7(ADC10)_27") (pintype "bidirectional"))
    )
    (net (code "84") (name "/REF") (class "Default")
      (node (ref "C22") (pin "1") (pinfunction "1_1") (pintype "passive"))
      (node (ref "U$6") (pin "42") (pinfunction "AREF_42") (pintype "bidirectional"))
    )
    (net (code "85") (name "/REN") (class "Default")
      (node (ref "IC1") (pin "13") (pinfunction "G_13") (pintype "input"))
      (node (ref "IC2") (pin "13") (pinfunction "G_13") (pintype "input"))
      (node (ref "IC3") (pin "13") (pinfunction "G_13") (pintype "input"))
      (node (ref "IC4") (pin "13") (pinfunction "G_13") (pintype "input"))
      (node (ref "IC5") (pin "13") (pinfunction "G_13") (pintype "input"))
      (node (ref "IC6") (pin "13") (pinfunction "G_13") (pintype "input"))
      (node (ref "IC7") (pin "13") (pinfunction "G_13") (pintype "input"))
      (node (ref "IC8") (pin "13") (pinfunction "G_13") (pintype "input"))
      (node (ref "REG1") (pin "1") (pinfunction "1_1") (pintype "passive"))
      (node (ref "REG2") (pin "1") (pinfunction "1_1") (pintype "passive"))
      (node (ref "U$6") (pin "26") (pinfunction "PD6(ADC9)_26") (pintype "bidirectional"))
    )
    (net (code "86") (name "/RST") (class "Default")
      (node (ref "J1") (pin "5") (pinfunction "5_5") (pintype "passive"))
      (node (ref "R7") (pin "2") (pinfunction "2_2") (pintype "passive"))
      (node (ref "S1") (pin "P$2") (pinfunction "2_P$2") (pintype "passive"))
      (node (ref "U$6") (pin "13") (pinfunction "~{RESET}_13") (pintype "bidirectional"))
    )
    (net (code "87") (name "/RX") (class "Default")
      (node (ref "SERIAL") (pin "1") (pinfunction "1_1") (pintype "passive"))
      (node (ref "U$6") (pin "20") (pinfunction "PD2(RX)_20") (pintype "bidirectional"))
    )
    (net (code "88") (name "/SBLUE") (class "Default")
      (node (ref "IC3") (pin "14") (pinfunction "SER_14") (pintype "input"))
      (node (ref "U$6") (pin "12") (pinfunction "PB7_12") (pintype "bidirectional"))
    )
    (net (code "89") (name "/SBLUE1") (class "Default")
      (node (ref "DAT1") (pin "1") (pinfunction "1_1") (pintype "passive"))
      (node (ref "DAT2") (pin "1") (pinfunction "1_1") (pintype "passive"))
      (node (ref "IC3") (pin "9") (pinfunction "QH*_9") (pintype "tri_state"))
      (node (ref "IC6") (pin "14") (pinfunction "SER_14") (pintype "input"))
    )
    (net (code "90") (name "/SCL") (class "Default")
      (node (ref "I2C") (pin "2") (pinfunction "2_2") (pintype "passive"))
      (node (ref "R20") (pin "2") (pinfunction "2_2") (pintype "passive"))
      (node (ref "U$2") (pin "6") (pinfunction "SCL_6") (pintype "bidirectional"))
      (node (ref "U$3") (pin "P6") (pinfunction "SCL_P6") (pintype "bidirectional"))
      (node (ref "U$6") (pin "18") (pinfunction "PD0(SCL)_18") (pintype "bidirectional"))
    )
    (net (code "91") (name "/SCLK") (class "Default")
      (node (ref "IC1") (pin "11") (pinfunction "SCK_11") (pintype "input"))
      (node (ref "IC2") (pin "11") (pinfunction "SCK_11") (pintype "input"))
      (node (ref "IC3") (pin "11") (pinfunction "SCK_11") (pintype "input"))
      (node (ref "IC4") (pin "11") (pinfunction "SCK_11") (pintype "input"))
      (node (ref "IC5") (pin "11") (pinfunction "SCK_11") (pintype "input"))
      (node (ref "IC6") (pin "11") (pinfunction "SCK_11") (pintype "input"))
      (node (ref "IC7") (pin "11") (pinfunction "SCK_11") (pintype "input"))
      (node (ref "IC8") (pin "11") (pinfunction "SCK_11") (pintype "input"))
      (node (ref "REG1") (pin "3") (pinfunction "3_3") (pintype "passive"))
      (node (ref "REG2") (pin "3") (pinfunction "3_3") (pintype "passive"))
      (node (ref "U$6") (pin "28") (pinfunction "PB4(ADC11)_28") (pintype "bidirectional"))
    )
    (net (code "92") (name "/SCLR") (class "Default")
      (node (ref "IC1") (pin "10") (pinfunction "SCL_10") (pintype "input"))
      (node (ref "IC2") (pin "10") (pinfunction "SCL_10") (pintype "input"))
      (node (ref "IC3") (pin "10") (pinfunction "SCL_10") (pintype "input"))
      (node (ref "IC4") (pin "10") (pinfunction "SCL_10") (pintype "input"))
      (node (ref "IC5") (pin "10") (pinfunction "SCL_10") (pintype "input"))
      (node (ref "IC6") (pin "10") (pinfunction "SCL_10") (pintype "input"))
      (node (ref "IC7") (pin "10") (pinfunction "SCL_10") (pintype "input"))
      (node (ref "IC8") (pin "10") (pinfunction "SCL_10") (pintype "input"))
      (node (ref "REG1") (pin "4") (pinfunction "4_4") (pintype "passive"))
      (node (ref "REG2") (pin "4") (pinfunction "4_4") (pintype "passive"))
      (node (ref "U$6") (pin "29") (pinfunction "PB5(ADC12)_29") (pintype "bidirectional"))
    )
    (net (code "93") (name "/SCOM") (class "Default")
      (node (ref "IC7") (pin "14") (pinfunction "SER_14") (pintype "input"))
      (node (ref "U$6") (pin "25") (pinfunction "PD4(ADC8)_25") (pintype "bidirectional"))
    )
    (net (code "94") (name "/SCOM1") (class "Default")
      (node (ref "DAT1") (pin "3") (pinfunction "3_3") (pintype "passive"))
      (node (ref "DAT2") (pin "3") (pinfunction "3_3") (pintype "passive"))
      (node (ref "IC7") (pin "9") (pinfunction "QH*_9") (pintype "tri_state"))
      (node (ref "IC8") (pin "14") (pinfunction "SER_14") (pintype "input"))
    )
    (net (code "95") (name "/SDA") (class "Default")
      (node (ref "I2C") (pin "1") (pinfunction "1_1") (pintype "passive"))
      (node (ref "R3") (pin "2") (pinfunction "2_2") (pintype "passive"))
      (node (ref "U$2") (pin "7") (pinfunction "SDA_7") (pintype "bidirectional"))
      (node (ref "U$3") (pin "P5") (pinfunction "SDA_P5") (pintype "bidirectional"))
      (node (ref "U$6") (pin "19") (pinfunction "PD1(SDA)_19") (pintype "bidirectional"))
    )
    (net (code "96") (name "/SGREEN") (class "Default")
      (node (ref "IC2") (pin "14") (pinfunction "SER_14") (pintype "input"))
      (node (ref "U$6") (pin "31") (pinfunction "PC6_31") (pintype "bidirectional"))
    )
    (net (code "97") (name "/SGREEN1") (class "Default")
      (node (ref "DAT1") (pin "4") (pinfunction "4_4") (pintype "passive"))
      (node (ref "DAT2") (pin "4") (pinfunction "4_4") (pintype "passive"))
      (node (ref "IC2") (pin "9") (pinfunction "QH*_9") (pintype "tri_state"))
      (node (ref "IC5") (pin "14") (pinfunction "SER_14") (pintype "input"))
    )
    (net (code "98") (name "/SPKR") (class "Default")
      (node (ref "SPEAKER") (pin "1") (pinfunction "1_1") (pintype "passive"))
      (node (ref "U$6") (pin "32") (pinfunction "PC7_32") (pintype "bidirectional"))
    )
    (net (code "99") (name "/SRED") (class "Default")
      (node (ref "IC1") (pin "14") (pinfunction "SER_14") (pintype "input"))
      (node (ref "U$6") (pin "30") (pinfunction "PB6(ADC13)_30") (pintype "bidirectional"))
    )
    (net (code "100") (name "/SRED1") (class "Default")
      (node (ref "DAT1") (pin "2") (pinfunction "2_2") (pintype "passive"))
      (node (ref "DAT2") (pin "2") (pinfunction "2_2") (pintype "passive"))
      (node (ref "IC1") (pin "9") (pinfunction "QH*_9") (pintype "tri_state"))
      (node (ref "IC4") (pin "14") (pinfunction "SER_14") (pintype "input"))
    )
    (net (code "101") (name "/TX") (class "Default")
      (node (ref "SERIAL") (pin "2") (pinfunction "2_2") (pintype "passive"))
      (node (ref "U$6") (pin "21") (pinfunction "PD3(TX)_21") (pintype "bidirectional"))
    )
    (net (code "102") (name "/TXLED") (class "Default")
      (node (ref "U$6") (pin "22") (pinfunction "PD5_22") (pintype "bidirectional"))
    )
    (net (code "103") (name "/VBAT") (class "Default")
      (node (ref "C18") (pin "1") (pinfunction "1_1") (pintype "passive"))
      (node (ref "C20") (pin "1") (pinfunction "1_1") (pintype "passive"))
      (node (ref "L1") (pin "P$2") (pinfunction "2_P$2") (pintype "passive"))
      (node (ref "LED4") (pin "A") (pinfunction "A_A") (pintype "passive"))
      (node (ref "R16") (pin "2") (pinfunction "2_2") (pintype "passive"))
      (node (ref "R19") (pin "2") (pinfunction "2_2") (pintype "passive"))
      (node (ref "R22") (pin "2") (pinfunction "2_2") (pintype "passive"))
      (node (ref "U$4") (pin "P") (pinfunction "P_P") (pintype "passive"))
      (node (ref "U2") (pin "5") (pinfunction "VIN_5") (pintype "power_in"))
    )
    (net (code "104") (name "/VBUS") (class "Default")
      (node (ref "C23") (pin "1") (pinfunction "1_1") (pintype "passive"))
      (node (ref "LED3") (pin "A") (pinfunction "A_A") (pintype "passive"))
      (node (ref "POW1") (pin "4") (pinfunction "4_4") (pintype "passive"))
      (node (ref "POW2") (pin "4") (pinfunction "4_4") (pintype "passive"))
      (node (ref "U$1") (pin "P1") (pinfunction "P$2_P1") (pintype "bidirectional"))
      (node (ref "U$6") (pin "2") (pinfunction "UVCC_2") (pintype "bidirectional"))
      (node (ref "U$6") (pin "7") (pinfunction "VBUS_7") (pintype "bidirectional"))
      (node (ref "U1") (pin "4") (pinfunction "VIN_4") (pintype "power_in"))
    )
    (net (code "105") (name "GND") (class "Default")
      (node (ref "BAT1") (pin "GND") (pinfunction "-_GND") (pintype "power_in"))
      (node (ref "BAT_IN") (pin "2") (pinfunction "2_2") (pintype "passive"))
      (node (ref "C1") (pin "2") (pinfunction "2_2") (pintype "passive"))
      (node (ref "C10") (pin "2") (pinfunction "2_2") (pintype "passive"))
      (node (ref "C12") (pin "2") (pinfunction "2_2") (pintype "passive"))
      (node (ref "C13") (pin "2") (pinfunction "2_2") (pintype "passive"))
      (node (ref "C16") (pin "2") (pinfunction "2_2") (pintype "passive"))
      (node (ref "C17") (pin "2") (pinfunction "2_2") (pintype "passive"))
      (node (ref "C19") (pin "2") (pinfunction "2_2") (pintype "passive"))
      (node (ref "C2") (pin "2") (pinfunction "2_2") (pintype "passive"))
      (node (ref "C20") (pin "2") (pinfunction "2_2") (pintype "passive"))
      (node (ref "C21") (pin "2") (pinfunction "2_2") (pintype "passive"))
      (node (ref "C22") (pin "2") (pinfunction "2_2") (pintype "passive"))
      (node (ref "C23") (pin "2") (pinfunction "2_2") (pintype "passive"))
      (node (ref "C3") (pin "2") (pinfunction "2_2") (pintype "passive"))
      (node (ref "C4") (pin "2") (pinfunction "2_2") (pintype "passive"))
      (node (ref "C5") (pin "2") (pinfunction "2_2") (pintype "passive"))
      (node (ref "C6") (pin "2") (pinfunction "2_2") (pintype "passive"))
      (node (ref "C7") (pin "2") (pinfunction "2_2") (pintype "passive"))
      (node (ref "C8") (pin "2") (pinfunction "2_2") (pintype "passive"))
      (node (ref "C9") (pin "2") (pinfunction "2_2") (pintype "passive"))
      (node (ref "IC1") (pin "8") (pinfunction "GND_8") (pintype "power_in"))
      (node (ref "IC10") (pin "3") (pinfunction "GND_3") (pintype "power_in"))
      (node (ref "IC11") (pin "3") (pinfunction "GND_3") (pintype "power_in"))
      (node (ref "IC12") (pin "3") (pinfunction "GND_3") (pintype "power_in"))
      (node (ref "IC2") (pin "8") (pinfunction "GND_8") (pintype "power_in"))
      (node (ref "IC3") (pin "8") (pinfunction "GND_8") (pintype "power_in"))
      (node (ref "IC4") (pin "8") (pinfunction "GND_8") (pintype "power_in"))
      (node (ref "IC5") (pin "8") (pinfunction "GND_8") (pintype "power_in"))
      (node (ref "IC6") (pin "8") (pinfunction "GND_8") (pintype "power_in"))
      (node (ref "IC7") (pin "8") (pinfunction "GND_8") (pintype "power_in"))
      (node (ref "IC8") (pin "8") (pinfunction "GND_8") (pintype "power_in"))
      (node (ref "IC9") (pin "2") (pinfunction "GND_2") (pintype "passive"))
      (node (ref "J1") (pin "6") (pinfunction "6_6") (pintype "passive"))
      (node (ref "JP2") (pin "1") (pinfunction "1_1") (pintype "passive"))
      (node (ref "JP3") (pin "1") (pinfunction "1_1") (pintype "passive"))
      (node (ref "LIGHT") (pin "2") (pinfunction "2_2") (pintype "passive"))
      (node (ref "MIC") (pin "2") (pinfunction "2_2") (pintype "passive"))
      (node (ref "POW1") (pin "1") (pinfunction "1_1") (pintype "passive"))
      (node (ref "POW2") (pin "1") (pinfunction "1_1") (pintype "passive"))
      (node (ref "R13") (pin "1") (pinfunction "1_1") (pintype "passive"))
      (node (ref "R14") (pin "1") (pinfunction "1_1") (pintype "passive"))
      (node (ref "R15") (pin "1") (pinfunction "1_1") (pintype "passive"))
      (node (ref "S1") (pin "P$1") (pinfunction "1_P$1") (pintype "passive"))
      (node (ref "SPEAKER") (pin "2") (pinfunction "2_2") (pintype "passive"))
      (node (ref "T1") (pin "E") (pinfunction "E_E") (pintype "passive"))
      (node (ref "U$1") (pin "P$1") (pinfunction "P$1_P$1") (pintype "bidirectional"))
      (node (ref "U$1") (pin "P$2") (pinfunction "P$1_P$2") (pintype "bidirectional"))
      (node (ref "U$1") (pin "P$3") (pinfunction "P$1_P$3") (pintype "bidirectional"))
      (node (ref "U$1") (pin "P$4") (pinfunction "P$1_P$4") (pintype "bidirectional"))
      (node (ref "U$1") (pin "P$5") (pinfunction "P$1_P$5") (pintype "bidirectional"))
      (node (ref "U$1") (pin "P$6") (pinfunction "P$1_P$6") (pintype "bidirectional"))
      (node (ref "U$1") (pin "P4") (pinfunction "P$1_P4") (pintype "bidirectional"))
      (node (ref "U$1") (pin "P5") (pinfunction "P$1_P5") (pintype "bidirectional"))
      (node (ref "U$2") (pin "1") (pinfunction "RES-GND_1") (pintype "bidirectional"))
      (node (ref "U$2") (pin "4") (pinfunction "AVSS_4") (pintype "bidirectional"))
      (node (ref "U$2") (pin "8") (pinfunction "DVSS_8") (pintype "bidirectional"))
      (node (ref "U$3") (pin "P4") (pinfunction "VSS_P4") (pintype "bidirectional"))
      (node (ref "U$6") (pin "15") (pinfunction "GND_15") (pintype "bidirectional"))
      (node (ref "U$6") (pin "23") (pinfunction "GND_23") (pintype "bidirectional"))
      (node (ref "U$6") (pin "33") (pinfunction "PE2/~{HWB}_33") (pintype "bidirectional"))
      (node (ref "U$6") (pin "35") (pinfunction "GND_35") (pintype "bidirectional"))
      (node (ref "U$6") (pin "43") (pinfunction "GND_43") (pintype "bidirectional"))
      (node (ref "U$6") (pin "5") (pinfunction "UGND_5") (pintype "bidirectional"))
      (node (ref "U1") (pin "2") (pinfunction "VSS_2") (pintype "power_in"))
      (node (ref "U2") (pin "11") (pinfunction "PAD_11") (pintype "power_in"))
      (node (ref "U2") (pin "12") (pinfunction "PAD_12") (pintype "power_in"))
      (node (ref "U2") (pin "13") (pinfunction "PAD_13") (pintype "power_in"))
      (node (ref "U2") (pin "14") (pinfunction "PAD_14") (pintype "power_in"))
      (node (ref "U2") (pin "15") (pinfunction "PAD_15") (pintype "power_in"))
      (node (ref "U2") (pin "4") (pinfunction "PGND_4") (pintype "power_in"))
      (node (ref "Y2") (pin "2") (pinfunction "2_2") (pintype "passive"))
    )
    (net (code "106") (name "Net-(BAT1-+)") (class "Default")
      (node (ref "BAT1") (pin "PWR@1") (pinfunction "+_PWR@1") (pintype "power_in"))
      (node (ref "U$3") (pin "P3") (pinfunction "VBAT_P3") (pintype "bidirectional"))
    )
    (net (code "107") (name "Net-(C11-Pad1)") (class "Default")
      (node (ref "C11") (pin "1") (pinfunction "1_1") (pintype "passive"))
      (node (ref "R8") (pin "1") (pinfunction "1_1") (pintype "passive"))
      (node (ref "T1") (pin "B") (pinfunction "B_B") (pintype "passive"))
    )
    (net (code "108") (name "Net-(C11-Pad2)") (class "Default")
      (node (ref "C11") (pin "2") (pinfunction "2_2") (pintype "passive"))
      (node (ref "MIC") (pin "1") (pinfunction "1_1") (pintype "passive"))
      (node (ref "R5") (pin "1") (pinfunction "1_1") (pintype "passive"))
    )
    (net (code "109") (name "Net-(IC4-QH*)") (class "Default")
      (node (ref "IC4") (pin "9") (pinfunction "QH*_9") (pintype "tri_state"))
      (node (ref "R_OUT") (pin "1") (pinfunction "1_1") (pintype "passive"))
    )
    (net (code "110") (name "Net-(IC5-QH*)") (class "Default")
      (node (ref "G_OUT") (pin "1") (pinfunction "1_1") (pintype "passive"))
      (node (ref "IC5") (pin "9") (pinfunction "QH*_9") (pintype "tri_state"))
    )
    (net (code "111") (name "Net-(IC6-QH*)") (class "Default")
      (node (ref "B_OUT") (pin "1") (pinfunction "1_1") (pintype "passive"))
      (node (ref "IC6") (pin "9") (pinfunction "QH*_9") (pintype "tri_state"))
    )
    (net (code "112") (name "Net-(IC7-QA)") (class "Default")
      (node (ref "IC7") (pin "15") (pinfunction "QA_15") (pintype "tri_state"))
      (node (ref "Q4") (pin "5") (pinfunction "B_5") (pintype "passive"))
    )
    (net (code "113") (name "Net-(IC7-QB)") (class "Default")
      (node (ref "IC7") (pin "1") (pinfunction "QB_1") (pintype "tri_state"))
      (node (ref "Q4") (pin "2") (pinfunction "B_2") (pintype "passive"))
    )
    (net (code "114") (name "Net-(IC7-QC)") (class "Default")
      (node (ref "IC7") (pin "2") (pinfunction "QC_2") (pintype "tri_state"))
      (node (ref "Q3") (pin "5") (pinfunction "B_5") (pintype "passive"))
    )
    (net (code "115") (name "Net-(IC7-QD)") (class "Default")
      (node (ref "IC7") (pin "3") (pinfunction "QD_3") (pintype "tri_state"))
      (node (ref "Q3") (pin "2") (pinfunction "B_2") (pintype "passive"))
    )
    (net (code "116") (name "Net-(IC7-QE)") (class "Default")
      (node (ref "IC7") (pin "4") (pinfunction "QE_4") (pintype "tri_state"))
      (node (ref "Q2") (pin "5") (pinfunction "B_5") (pintype "passive"))
    )
    (net (code "117") (name "Net-(IC7-QF)") (class "Default")
      (node (ref "IC7") (pin "5") (pinfunction "QF_5") (pintype "tri_state"))
      (node (ref "Q2") (pin "2") (pinfunction "B_2") (pintype "passive"))
    )
    (net (code "118") (name "Net-(IC7-QG)") (class "Default")
      (node (ref "IC7") (pin "6") (pinfunction "QG_6") (pintype "tri_state"))
      (node (ref "Q1") (pin "5") (pinfunction "B_5") (pintype "passive"))
    )
    (net (code "119") (name "Net-(IC7-QH)") (class "Default")
      (node (ref "IC7") (pin "7") (pinfunction "QH_7") (pintype "tri_state"))
      (node (ref "Q1") (pin "2") (pinfunction "B_2") (pintype "passive"))
    )
    (net (code "120") (name "Net-(IC8-QA)") (class "Default")
      (node (ref "IC8") (pin "15") (pinfunction "QA_15") (pintype "tri_state"))
      (node (ref "Q8") (pin "5") (pinfunction "B_5") (pintype "passive"))
    )
    (net (code "121") (name "Net-(IC8-QB)") (class "Default")
      (node (ref "IC8") (pin "1") (pinfunction "QB_1") (pintype "tri_state"))
      (node (ref "Q8") (pin "2") (pinfunction "B_2") (pintype "passive"))
    )
    (net (code "122") (name "Net-(IC8-QC)") (class "Default")
      (node (ref "IC8") (pin "2") (pinfunction "QC_2") (pintype "tri_state"))
      (node (ref "Q7") (pin "5") (pinfunction "B_5") (pintype "passive"))
    )
    (net (code "123") (name "Net-(IC8-QD)") (class "Default")
      (node (ref "IC8") (pin "3") (pinfunction "QD_3") (pintype "tri_state"))
      (node (ref "Q7") (pin "2") (pinfunction "B_2") (pintype "passive"))
    )
    (net (code "124") (name "Net-(IC8-QE)") (class "Default")
      (node (ref "IC8") (pin "4") (pinfunction "QE_4") (pintype "tri_state"))
      (node (ref "Q6") (pin "5") (pinfunction "B_5") (pintype "passive"))
    )
    (net (code "125") (name "Net-(IC8-QF)") (class "Default")
      (node (ref "IC8") (pin "5") (pinfunction "QF_5") (pintype "tri_state"))
      (node (ref "Q6") (pin "2") (pinfunction "B_2") (pintype "passive"))
    )
    (net (code "126") (name "Net-(IC8-QG)") (class "Default")
      (node (ref "IC8") (pin "6") (pinfunction "QG_6") (pintype "tri_state"))
      (node (ref "Q5") (pin "5") (pinfunction "B_5") (pintype "passive"))
    )
    (net (code "127") (name "Net-(IC8-QH)") (class "Default")
      (node (ref "IC8") (pin "7") (pinfunction "QH_7") (pintype "tri_state"))
      (node (ref "Q5") (pin "2") (pinfunction "B_2") (pintype "passive"))
    )
    (net (code "128") (name "Net-(IC8-QH*)") (class "Default")
      (node (ref "C_OUT") (pin "1") (pinfunction "1_1") (pintype "passive"))
      (node (ref "IC8") (pin "9") (pinfunction "QH*_9") (pintype "tri_state"))
    )
    (net (code "129") (name "Net-(IC9-CB)") (class "Default")
      (node (ref "C13") (pin "1") (pinfunction "1_1") (pintype "passive"))
      (node (ref "IC9") (pin "4") (pinfunction "CB_4") (pintype "input"))
    )
    (net (code "130") (name "Net-(L1-1)") (class "Default")
      (node (ref "L1") (pin "P$1") (pinfunction "1_P$1") (pintype "passive"))
      (node (ref "U2") (pin "3") (pinfunction "L_3") (pintype "passive"))
    )
    (net (code "131") (name "Net-(LED3-PadC)") (class "Default")
      (node (ref "LED3") (pin "C") (pinfunction "C_C") (pintype "passive"))
      (node (ref "R13") (pin "2") (pinfunction "2_2") (pintype "passive"))
    )
    (net (code "132") (name "Net-(LED4-PadC)") (class "Default")
      (node (ref "LED4") (pin "C") (pinfunction "C_C") (pintype "passive"))
      (node (ref "R14") (pin "2") (pinfunction "2_2") (pintype "passive"))
    )
    (net (code "133") (name "Net-(U$1-P$3)") (class "Default")
      (node (ref "R2") (pin "1") (pinfunction "1_1") (pintype "passive"))
      (node (ref "U$1") (pin "P2") (pinfunction "P$3_P2") (pintype "bidirectional"))
    )
    (net (code "134") (name "Net-(U$1-P$4)") (class "Default")
      (node (ref "R6") (pin "1") (pinfunction "1_1") (pintype "passive"))
      (node (ref "U$1") (pin "P3") (pinfunction "P$4_P3") (pintype "bidirectional"))
    )
    (net (code "135") (name "Net-(U$3-OSCI)") (class "Default")
      (node (ref "U$3") (pin "P1") (pinfunction "OSCI_P1") (pintype "bidirectional"))
      (node (ref "Y1") (pin "2") (pinfunction "2_2") (pintype "passive"))
    )
    (net (code "136") (name "Net-(U$3-OSCO)") (class "Default")
      (node (ref "U$3") (pin "P2") (pinfunction "OSCO_P2") (pintype "bidirectional"))
      (node (ref "Y1") (pin "1") (pinfunction "1_1") (pintype "passive"))
    )
    (net (code "137") (name "Net-(U$6-D+)") (class "Default")
      (node (ref "R6") (pin "2") (pinfunction "2_2") (pintype "passive"))
      (node (ref "U$6") (pin "4") (pinfunction "D+_4") (pintype "bidirectional"))
    )
    (net (code "138") (name "Net-(U$6-D-)") (class "Default")
      (node (ref "R2") (pin "2") (pinfunction "2_2") (pintype "passive"))
      (node (ref "U$6") (pin "3") (pinfunction "D-_3") (pintype "bidirectional"))
    )
    (net (code "139") (name "Net-(U$6-UCAP)") (class "Default")
      (node (ref "C19") (pin "1") (pinfunction "1_1") (pintype "passive"))
      (node (ref "U$6") (pin "6") (pinfunction "UCAP_6") (pintype "bidirectional"))
    )
    (net (code "140") (name "Net-(U$6-XTAL1)") (class "Default")
      (node (ref "U$6") (pin "17") (pinfunction "XTAL1_17") (pintype "bidirectional"))
      (node (ref "Y2") (pin "1") (pinfunction "1_1") (pintype "passive"))
    )
    (net (code "141") (name "Net-(U$6-XTAL2)") (class "Default")
      (node (ref "U$6") (pin "16") (pinfunction "XTAL2_16") (pintype "bidirectional"))
      (node (ref "Y2") (pin "3") (pinfunction "3_3") (pintype "passive"))
    )
    (net (code "142") (name "Net-(U1-PROG)") (class "Default")
      (node (ref "R15") (pin "2") (pinfunction "2_2") (pintype "passive"))
      (node (ref "U1") (pin "5") (pinfunction "PROG_5") (pintype "input"))
    )
    (net (code "143") (name "Net-(U2-FB)") (class "Default")
      (node (ref "R17") (pin "1") (pinfunction "1_1") (pintype "passive"))
      (node (ref "R18") (pin "2") (pinfunction "2_2") (pintype "passive"))
      (node (ref "U2") (pin "10") (pinfunction "FB_10") (pintype "passive"))
    )
    (net (code "144") (name "Net-(U2-UVLO)") (class "Default")
      (node (ref "C18") (pin "2") (pinfunction "2_2") (pintype "passive"))
      (node (ref "R22") (pin "1") (pinfunction "1_1") (pintype "passive"))
      (node (ref "R23") (pin "2") (pinfunction "2_2") (pintype "passive"))
      (node (ref "U2") (pin "7") (pinfunction "UVLO_7") (pintype "passive"))
    )
    (net (code "145") (name "Net-(U2-VAUX)") (class "Default")
      (node (ref "C21") (pin "1") (pinfunction "1_1") (pintype "passive"))
      (node (ref "U2") (pin "1") (pinfunction "VAUX_1") (pintype "passive"))
    )
    (net (code "146") (name "VCC") (class "Default")
      (node (ref "C1") (pin "1") (pinfunction "1_1") (pintype "passive"))
      (node (ref "C16") (pin "1") (pinfunction "1_1") (pintype "passive"))
      (node (ref "C2") (pin "1") (pinfunction "1_1") (pintype "passive"))
      (node (ref "C3") (pin "1") (pinfunction "1_1") (pintype "passive"))
      (node (ref "C4") (pin "1") (pinfunction "1_1") (pintype "passive"))
      (node (ref "C5") (pin "1") (pinfunction "1_1") (pintype "passive"))
      (node (ref "C6") (pin "1") (pinfunction "1_1") (pintype "passive"))
      (node (ref "C7") (pin "1") (pinfunction "1_1") (pintype "passive"))
      (node (ref "C8") (pin "1") (pinfunction "1_1") (pintype "passive"))
      (node (ref "IC1") (pin "16") (pinfunction "VCC_16") (pintype "power_in"))
      (node (ref "IC10") (pin "1") (pinfunction "VCC_1") (pintype "power_in"))
      (node (ref "IC11") (pin "1") (pinfunction "VCC_1") (pintype "power_in"))
      (node (ref "IC12") (pin "1") (pinfunction "VCC_1") (pintype "power_in"))
      (node (ref "IC2") (pin "16") (pinfunction "VCC_16") (pintype "power_in"))
      (node (ref "IC3") (pin "16") (pinfunction "VCC_16") (pintype "power_in"))
      (node (ref "IC4") (pin "16") (pinfunction "VCC_16") (pintype "power_in"))
      (node (ref "IC5") (pin "16") (pinfunction "VCC_16") (pintype "power_in"))
      (node (ref "IC6") (pin "16") (pinfunction "VCC_16") (pintype "power_in"))
      (node (ref "IC7") (pin "16") (pinfunction "VCC_16") (pintype "power_in"))
      (node (ref "IC8") (pin "16") (pinfunction "VCC_16") (pintype "power_in"))
      (node (ref "IC9") (pin "1") (pinfunction "VIN_1") (pintype "input"))
      (node (ref "IC9") (pin "3") (pinfunction "CE_3") (pintype "input"))
      (node (ref "J1") (pin "2") (pinfunction "2_2") (pintype "passive"))
      (node (ref "POW1") (pin "2") (pinfunction "2_2") (pintype "passive"))
      (node (ref "POW2") (pin "2") (pinfunction "2_2") (pintype "passive"))
      (node (ref "Q1") (pin "1") (pinfunction "E_1") (pintype "passive"))
      (node (ref "Q1") (pin "4") (pinfunction "E_4") (pintype "passive"))
      (node (ref "Q2") (pin "1") (pinfunction "E_1") (pintype "passive"))
      (node (ref "Q2") (pin "4") (pinfunction "E_4") (pintype "passive"))
      (node (ref "Q3") (pin "1") (pinfunction "E_1") (pintype "passive"))
      (node (ref "Q3") (pin "4") (pinfunction "E_4") (pintype "passive"))
      (node (ref "Q4") (pin "1") (pinfunction "E_1") (pintype "passive"))
      (node (ref "Q4") (pin "4") (pinfunction "E_4") (pintype "passive"))
      (node (ref "Q5") (pin "1") (pinfunction "E_1") (pintype "passive"))
      (node (ref "Q5") (pin "4") (pinfunction "E_4") (pintype "passive"))
      (node (ref "Q6") (pin "1") (pinfunction "E_1") (pintype "passive"))
      (node (ref "Q6") (pin "4") (pinfunction "E_4") (pintype "passive"))
      (node (ref "Q7") (pin "1") (pinfunction "E_1") (pintype "passive"))
      (node (ref "Q7") (pin "4") (pinfunction "E_4") (pintype "passive"))
      (node (ref "Q8") (pin "1") (pinfunction "E_1") (pintype "passive"))
      (node (ref "Q8") (pin "4") (pinfunction "E_4") (pintype "passive"))
      (node (ref "R10") (pin "2") (pinfunction "2_2") (pintype "passive"))
      (node (ref "R17") (pin "2") (pinfunction "2_2") (pintype "passive"))
      (node (ref "R20") (pin "1") (pinfunction "1_1") (pintype "passive"))
      (node (ref "R3") (pin "1") (pinfunction "1_1") (pintype "passive"))
      (node (ref "R5") (pin "2") (pinfunction "2_2") (pintype "passive"))
      (node (ref "R7") (pin "1") (pinfunction "1_1") (pintype "passive"))
      (node (ref "R8") (pin "2") (pinfunction "2_2") (pintype "passive"))
      (node (ref "R9") (pin "2") (pinfunction "2_2") (pintype "passive"))
      (node (ref "U$3") (pin "P8") (pinfunction "VDD_P8") (pintype "bidirectional"))
      (node (ref "U$6") (pin "14") (pinfunction "VCC_14") (pintype "bidirectional"))
      (node (ref "U$6") (pin "24") (pinfunction "AVCC_24") (pintype "bidirectional"))
      (node (ref "U$6") (pin "34") (pinfunction "VCC_34") (pintype "bidirectional"))
      (node (ref "U$6") (pin "44") (pinfunction "AVCC_44") (pintype "bidirectional"))
      (node (ref "U2") (pin "2") (pinfunction "VOUT_2") (pintype "passive"))
    )
    (net (code "147") (name "unconnected-(U$2-NC-Pad2)") (class "Default")
      (node (ref "U$2") (pin "2") (pinfunction "NC_2") (pintype "bidirectional"))
    )
    (net (code "148") (name "unconnected-(U$2-RES-Pad10)") (class "Default")
      (node (ref "U$2") (pin "10") (pinfunction "RES_10") (pintype "bidirectional"))
    )
    (net (code "149") (name "unconnected-(U$4-PadS)") (class "Default")
      (node (ref "U$4") (pin "S") (pinfunction "S_S") (pintype "passive"))
    )
    (net (code "150") (name "unconnected-(U1-STAT-Pad1)") (class "Default")
      (node (ref "U1") (pin "1") (pinfunction "STAT_1") (pintype "output"))
    )
  )
)
